# double100.net
KiCad netlist of a schematic drawn in EAGLE
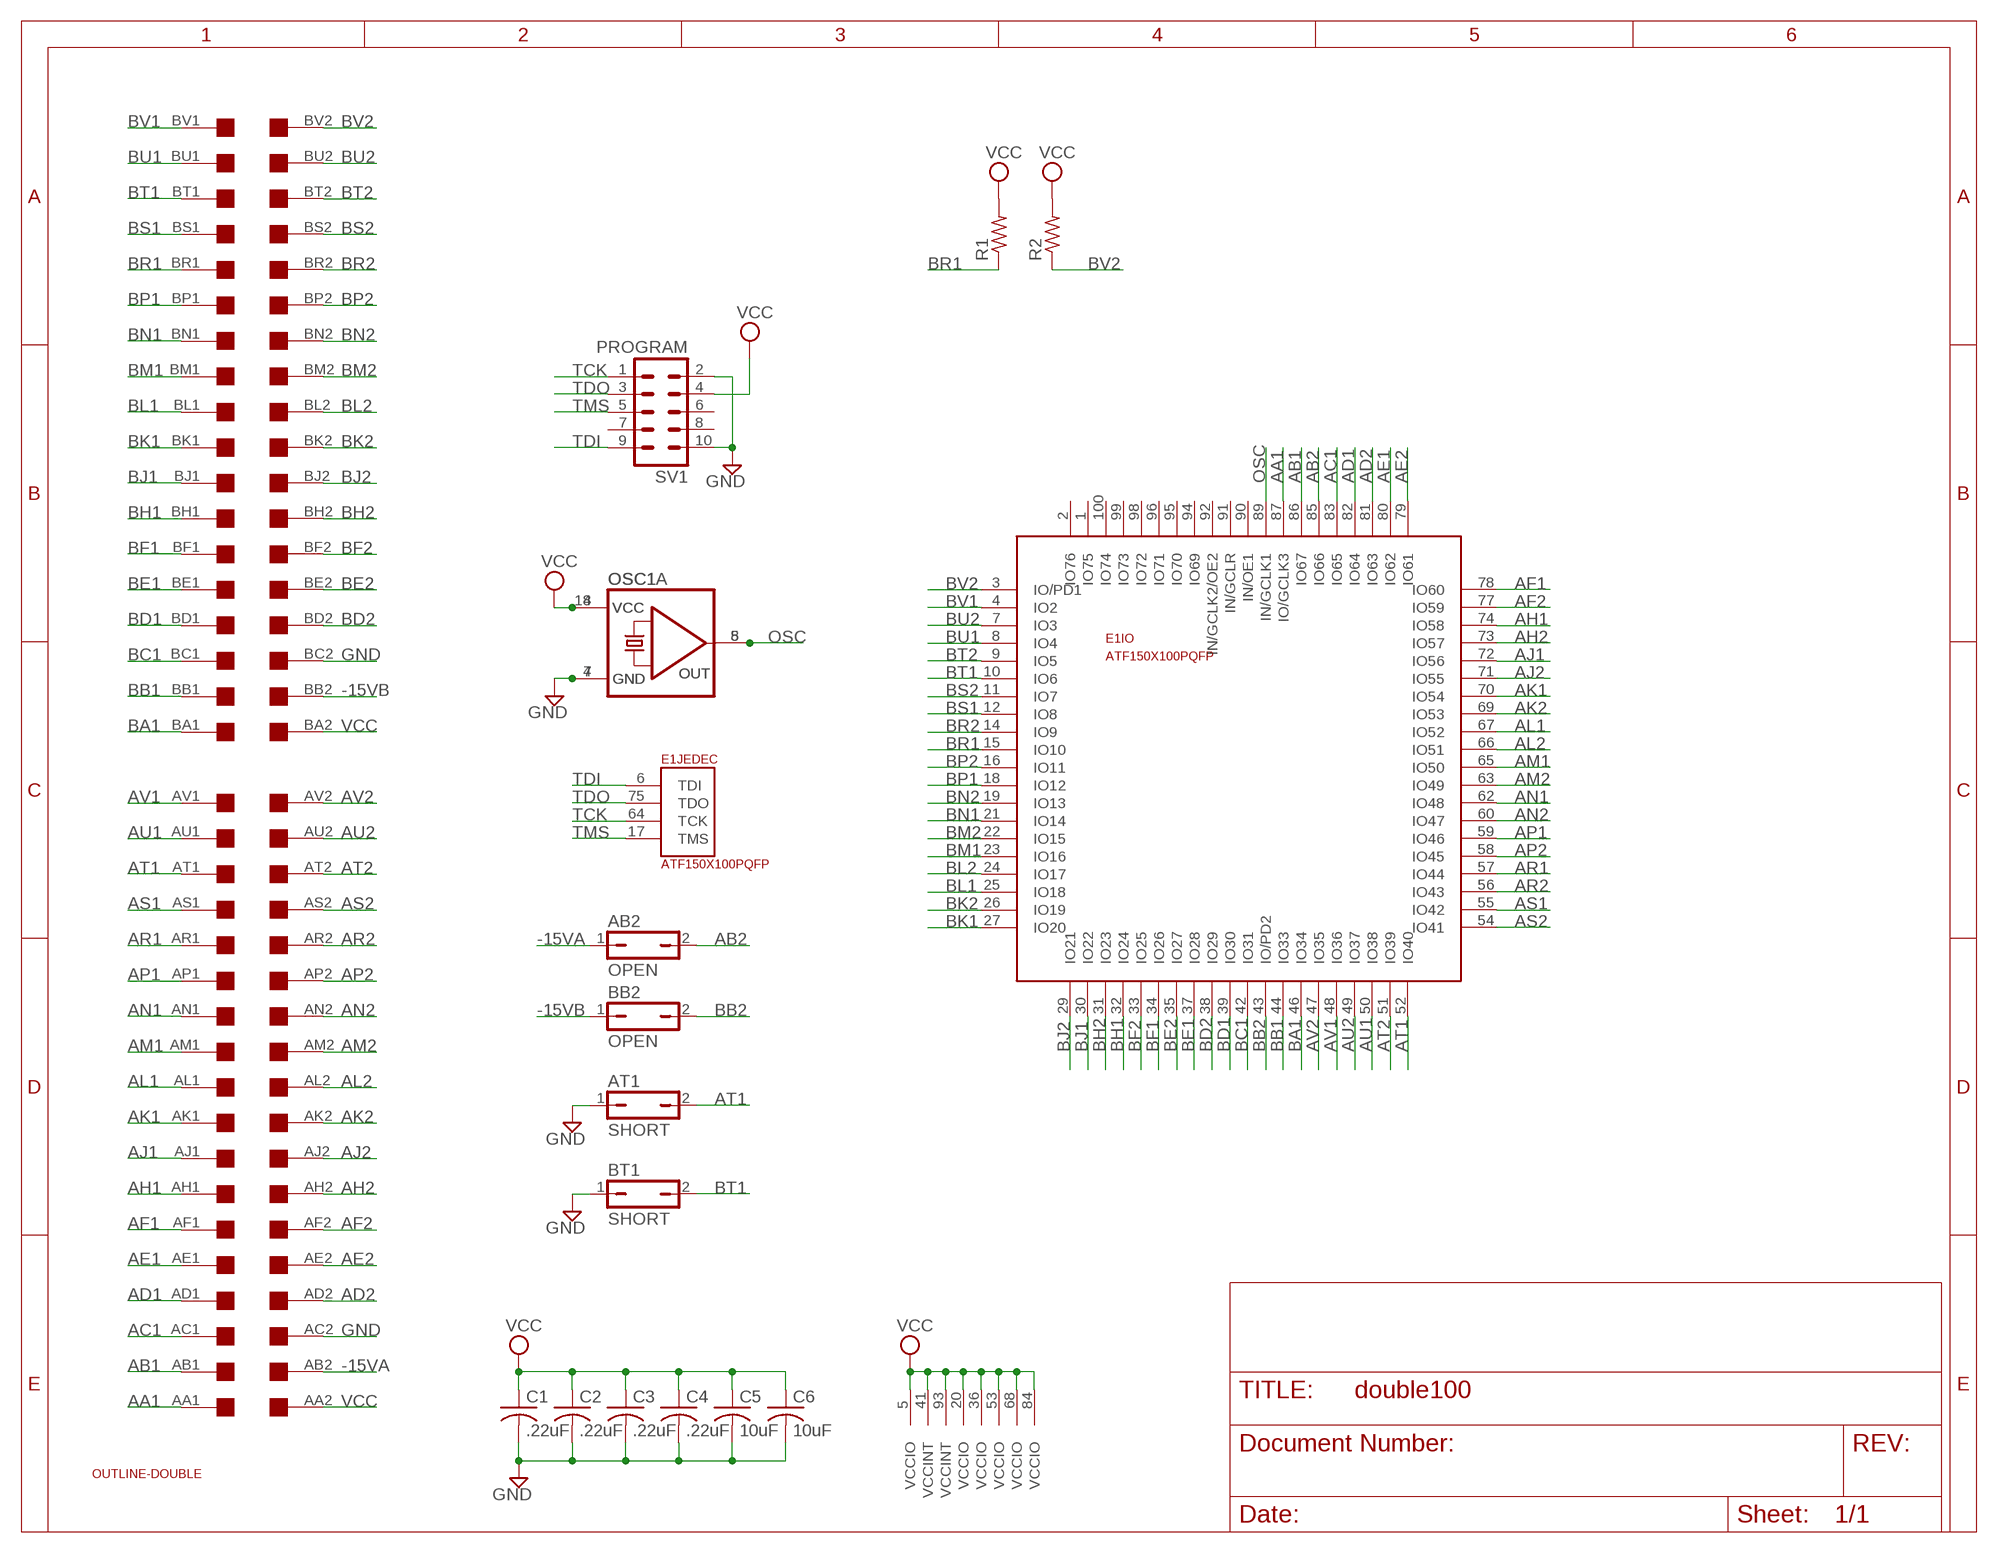
[diagram p0: schematic, sheet 1]

(export (version "E")
  (design (tool "Eeschema 10.0.6"))
  (components
    (comp (ref "AB2")
      (value "OPEN")
      (footprint "eagle-import:JP1")
      (libsource (lib "eagle-import") (part "JP1Q"))
    )
    (comp (ref "AT1")
      (value "SHORT")
      (footprint "eagle-import:JP1")
      (libsource (lib "eagle-import") (part "JP1Q"))
    )
    (comp (ref "BB2")
      (value "OPEN")
      (footprint "eagle-import:JP1")
      (libsource (lib "eagle-import") (part "JP1Q"))
    )
    (comp (ref "BT1")
      (value "SHORT")
      (footprint "eagle-import:JP1")
      (libsource (lib "eagle-import") (part "JP1Q"))
    )
    (comp (ref "C1")
      (value ".22uF")
      (footprint "eagle-import:C0805")
      (libsource (lib "eagle-import") (part "C-USC0805"))
    )
    (comp (ref "C2")
      (value ".22uF")
      (footprint "eagle-import:C0805")
      (libsource (lib "eagle-import") (part "C-USC0805"))
    )
    (comp (ref "C3")
      (value ".22uF")
      (footprint "eagle-import:C0805")
      (libsource (lib "eagle-import") (part "C-USC0805"))
    )
    (comp (ref "C4")
      (value ".22uF")
      (footprint "eagle-import:C0805")
      (libsource (lib "eagle-import") (part "C-USC0805"))
    )
    (comp (ref "C5")
      (value "10uF")
      (footprint "eagle-import:C0805")
      (libsource (lib "eagle-import") (part "C-USC0805"))
    )
    (comp (ref "C6")
      (value "10uF")
      (footprint "eagle-import:C0805")
      (libsource (lib "eagle-import") (part "C-USC0805"))
    )
    (comp (ref "E1")
      (value "ATF150X100PQFP")
      (footprint "eagle-import:PQFP-100")
      (libsource (lib "eagle-import") (part "ATF150X100PQFP"))
    )
    (comp (ref "OSC1")
      (value "QG5460")
      (footprint "eagle-import:DIL08S")
      (libsource (lib "eagle-import") (part "QG5460"))
    )
    (comp (ref "OSC1A")
      (value "QG5860")
      (footprint "eagle-import:DIL14S")
      (libsource (lib "eagle-import") (part "QG5860"))
    )
    (comp (ref "R1")
      (value "R-US_0207/10")
      (footprint "eagle-import:0207_10")
      (libsource (lib "eagle-import") (part "R-US_0207/10"))
    )
    (comp (ref "R2")
      (value "R-US_0207/10")
      (footprint "eagle-import:0207_10")
      (libsource (lib "eagle-import") (part "R-US_0207/10"))
    )
    (comp (ref "SV1")
      (value "PROGRAM")
      (footprint "eagle-import:ML10")
      (libsource (lib "eagle-import") (part "ML10"))
    )
    (comp (ref "U$1")
      (value "DOUBLE")
      (footprint "eagle-import:EDGE-CON4")
      (libsource (lib "eagle-import") (part "DOUBLE"))
    )
    (comp (ref "U$3")
      (value "OUTLINE-DOUBLE")
      (footprint "eagle-import:DOUBLE")
      (libsource (lib "eagle-import") (part "OUTLINE-DOUBLE"))
    )
  )
  (nets
    (net (code "1") (name "/-15VA") (class "Default")
      (node (ref "AB2") (pin "1") (pinfunction "1_1") (pintype "passive"))
      (node (ref "U$1") (pin "AB2") (pinfunction "1_AB2") (pintype "bidirectional"))
    )
    (net (code "2") (name "/-15VB") (class "Default")
      (node (ref "BB2") (pin "1") (pinfunction "1_1") (pintype "passive"))
      (node (ref "U$1") (pin "BB2") (pinfunction "1_BB2") (pintype "bidirectional"))
    )
    (net (code "3") (name "/AA1") (class "Default")
      (node (ref "E1") (pin "87") (pinfunction "IO/GCLK3_87") (pintype "bidirectional"))
      (node (ref "U$1") (pin "AA1") (pinfunction "1_AA1") (pintype "bidirectional"))
    )
    (net (code "4") (name "/AB1") (class "Default")
      (node (ref "E1") (pin "86") (pinfunction "IO67_86") (pintype "bidirectional"))
      (node (ref "U$1") (pin "AB1") (pinfunction "1_AB1") (pintype "bidirectional"))
    )
    (net (code "5") (name "/AB2") (class "Default")
      (node (ref "AB2") (pin "2") (pinfunction "2_2") (pintype "passive"))
      (node (ref "E1") (pin "85") (pinfunction "IO66_85") (pintype "bidirectional"))
    )
    (net (code "6") (name "/AC1") (class "Default")
      (node (ref "E1") (pin "83") (pinfunction "IO65_83") (pintype "bidirectional"))
      (node (ref "U$1") (pin "AC1") (pinfunction "1_AC1") (pintype "bidirectional"))
    )
    (net (code "7") (name "/AD1") (class "Default")
      (node (ref "E1") (pin "82") (pinfunction "IO64_82") (pintype "bidirectional"))
      (node (ref "U$1") (pin "AD1") (pinfunction "1_AD1") (pintype "bidirectional"))
    )
    (net (code "8") (name "/AD2") (class "Default")
      (node (ref "E1") (pin "81") (pinfunction "IO63_81") (pintype "bidirectional"))
      (node (ref "U$1") (pin "AD2") (pinfunction "1_AD2") (pintype "bidirectional"))
    )
    (net (code "9") (name "/AE1") (class "Default")
      (node (ref "E1") (pin "80") (pinfunction "IO62_80") (pintype "bidirectional"))
      (node (ref "U$1") (pin "AE1") (pinfunction "1_AE1") (pintype "bidirectional"))
    )
    (net (code "10") (name "/AE2") (class "Default")
      (node (ref "E1") (pin "79") (pinfunction "IO61_79") (pintype "bidirectional"))
      (node (ref "U$1") (pin "AE2") (pinfunction "1_AE2") (pintype "bidirectional"))
    )
    (net (code "11") (name "/AF1") (class "Default")
      (node (ref "E1") (pin "78") (pinfunction "IO60_78") (pintype "bidirectional"))
      (node (ref "U$1") (pin "AF1") (pinfunction "1_AF1") (pintype "bidirectional"))
    )
    (net (code "12") (name "/AF2") (class "Default")
      (node (ref "E1") (pin "77") (pinfunction "IO59_77") (pintype "bidirectional"))
      (node (ref "U$1") (pin "AF2") (pinfunction "1_AF2") (pintype "bidirectional"))
    )
    (net (code "13") (name "/AH1") (class "Default")
      (node (ref "E1") (pin "74") (pinfunction "IO58_74") (pintype "bidirectional"))
      (node (ref "U$1") (pin "AH1") (pinfunction "1_AH1") (pintype "bidirectional"))
    )
    (net (code "14") (name "/AH2") (class "Default")
      (node (ref "E1") (pin "73") (pinfunction "IO57_73") (pintype "bidirectional"))
      (node (ref "U$1") (pin "AH2") (pinfunction "1_AH2") (pintype "bidirectional"))
    )
    (net (code "15") (name "/AJ1") (class "Default")
      (node (ref "E1") (pin "72") (pinfunction "IO56_72") (pintype "bidirectional"))
      (node (ref "U$1") (pin "AJ1") (pinfunction "1_AJ1") (pintype "bidirectional"))
    )
    (net (code "16") (name "/AJ2") (class "Default")
      (node (ref "E1") (pin "71") (pinfunction "IO55_71") (pintype "bidirectional"))
      (node (ref "U$1") (pin "AJ2") (pinfunction "1_AJ2") (pintype "bidirectional"))
    )
    (net (code "17") (name "/AK1") (class "Default")
      (node (ref "E1") (pin "70") (pinfunction "IO54_70") (pintype "bidirectional"))
      (node (ref "U$1") (pin "AK1") (pinfunction "1_AK1") (pintype "bidirectional"))
    )
    (net (code "18") (name "/AK2") (class "Default")
      (node (ref "E1") (pin "69") (pinfunction "IO53_69") (pintype "bidirectional"))
      (node (ref "U$1") (pin "AK2") (pinfunction "1_AK2") (pintype "bidirectional"))
    )
    (net (code "19") (name "/AL1") (class "Default")
      (node (ref "E1") (pin "67") (pinfunction "IO52_67") (pintype "bidirectional"))
      (node (ref "U$1") (pin "AL1") (pinfunction "1_AL1") (pintype "bidirectional"))
    )
    (net (code "20") (name "/AL2") (class "Default")
      (node (ref "E1") (pin "66") (pinfunction "IO51_66") (pintype "bidirectional"))
      (node (ref "U$1") (pin "AL2") (pinfunction "1_AL2") (pintype "bidirectional"))
    )
    (net (code "21") (name "/AM1") (class "Default")
      (node (ref "E1") (pin "65") (pinfunction "IO50_65") (pintype "bidirectional"))
      (node (ref "U$1") (pin "AM1") (pinfunction "1_AM1") (pintype "bidirectional"))
    )
    (net (code "22") (name "/AM2") (class "Default")
      (node (ref "E1") (pin "63") (pinfunction "IO49_63") (pintype "bidirectional"))
      (node (ref "U$1") (pin "AM2") (pinfunction "1_AM2") (pintype "bidirectional"))
    )
    (net (code "23") (name "/AN1") (class "Default")
      (node (ref "E1") (pin "62") (pinfunction "IO48_62") (pintype "bidirectional"))
      (node (ref "U$1") (pin "AN1") (pinfunction "1_AN1") (pintype "bidirectional"))
    )
    (net (code "24") (name "/AN2") (class "Default")
      (node (ref "E1") (pin "60") (pinfunction "IO47_60") (pintype "bidirectional"))
      (node (ref "U$1") (pin "AN2") (pinfunction "1_AN2") (pintype "bidirectional"))
    )
    (net (code "25") (name "/AP1") (class "Default")
      (node (ref "E1") (pin "59") (pinfunction "IO46_59") (pintype "bidirectional"))
      (node (ref "U$1") (pin "AP1") (pinfunction "1_AP1") (pintype "bidirectional"))
    )
    (net (code "26") (name "/AP2") (class "Default")
      (node (ref "E1") (pin "58") (pinfunction "IO45_58") (pintype "bidirectional"))
      (node (ref "U$1") (pin "AP2") (pinfunction "1_AP2") (pintype "bidirectional"))
    )
    (net (code "27") (name "/AR1") (class "Default")
      (node (ref "E1") (pin "57") (pinfunction "IO44_57") (pintype "bidirectional"))
      (node (ref "U$1") (pin "AR1") (pinfunction "1_AR1") (pintype "bidirectional"))
    )
    (net (code "28") (name "/AR2") (class "Default")
      (node (ref "E1") (pin "56") (pinfunction "IO43_56") (pintype "bidirectional"))
      (node (ref "U$1") (pin "AR2") (pinfunction "1_AR2") (pintype "bidirectional"))
    )
    (net (code "29") (name "/AS1") (class "Default")
      (node (ref "E1") (pin "55") (pinfunction "IO42_55") (pintype "bidirectional"))
      (node (ref "U$1") (pin "AS1") (pinfunction "1_AS1") (pintype "bidirectional"))
    )
    (net (code "30") (name "/AS2") (class "Default")
      (node (ref "E1") (pin "54") (pinfunction "IO41_54") (pintype "bidirectional"))
      (node (ref "U$1") (pin "AS2") (pinfunction "1_AS2") (pintype "bidirectional"))
    )
    (net (code "31") (name "/AT1") (class "Default")
      (node (ref "AT1") (pin "2") (pinfunction "2_2") (pintype "passive"))
      (node (ref "E1") (pin "52") (pinfunction "IO40_52") (pintype "bidirectional"))
      (node (ref "U$1") (pin "AT1") (pinfunction "1_AT1") (pintype "bidirectional"))
    )
    (net (code "32") (name "/AT2") (class "Default")
      (node (ref "E1") (pin "51") (pinfunction "IO39_51") (pintype "bidirectional"))
      (node (ref "U$1") (pin "AT2") (pinfunction "1_AT2") (pintype "bidirectional"))
    )
    (net (code "33") (name "/AU1") (class "Default")
      (node (ref "E1") (pin "50") (pinfunction "IO38_50") (pintype "bidirectional"))
      (node (ref "U$1") (pin "AU1") (pinfunction "1_AU1") (pintype "bidirectional"))
    )
    (net (code "34") (name "/AU2") (class "Default")
      (node (ref "E1") (pin "49") (pinfunction "IO37_49") (pintype "bidirectional"))
      (node (ref "U$1") (pin "AU2") (pinfunction "1_AU2") (pintype "bidirectional"))
    )
    (net (code "35") (name "/AV1") (class "Default")
      (node (ref "E1") (pin "48") (pinfunction "IO36_48") (pintype "bidirectional"))
      (node (ref "U$1") (pin "AV1") (pinfunction "1_AV1") (pintype "bidirectional"))
    )
    (net (code "36") (name "/AV2") (class "Default")
      (node (ref "E1") (pin "47") (pinfunction "IO35_47") (pintype "bidirectional"))
      (node (ref "U$1") (pin "AV2") (pinfunction "1_AV2") (pintype "bidirectional"))
    )
    (net (code "37") (name "/BA1") (class "Default")
      (node (ref "E1") (pin "46") (pinfunction "IO34_46") (pintype "bidirectional"))
      (node (ref "U$1") (pin "BA1") (pinfunction "1_BA1") (pintype "bidirectional"))
    )
    (net (code "38") (name "/BB1") (class "Default")
      (node (ref "E1") (pin "44") (pinfunction "IO33_44") (pintype "bidirectional"))
      (node (ref "U$1") (pin "BB1") (pinfunction "1_BB1") (pintype "bidirectional"))
    )
    (net (code "39") (name "/BB2") (class "Default")
      (node (ref "BB2") (pin "2") (pinfunction "2_2") (pintype "passive"))
      (node (ref "E1") (pin "43") (pinfunction "IO/PD2_43") (pintype "bidirectional"))
    )
    (net (code "40") (name "/BC1") (class "Default")
      (node (ref "E1") (pin "42") (pinfunction "IO31_42") (pintype "bidirectional"))
      (node (ref "U$1") (pin "BC1") (pinfunction "1_BC1") (pintype "bidirectional"))
    )
    (net (code "41") (name "/BD1") (class "Default")
      (node (ref "E1") (pin "39") (pinfunction "IO30_39") (pintype "bidirectional"))
      (node (ref "U$1") (pin "BD1") (pinfunction "1_BD1") (pintype "bidirectional"))
    )
    (net (code "42") (name "/BD2") (class "Default")
      (node (ref "E1") (pin "38") (pinfunction "IO29_38") (pintype "bidirectional"))
      (node (ref "U$1") (pin "BD2") (pinfunction "1_BD2") (pintype "bidirectional"))
    )
    (net (code "43") (name "/BE1") (class "Default")
      (node (ref "E1") (pin "37") (pinfunction "IO28_37") (pintype "bidirectional"))
      (node (ref "U$1") (pin "BE1") (pinfunction "1_BE1") (pintype "bidirectional"))
    )
    (net (code "44") (name "/BE2") (class "Default")
      (node (ref "E1") (pin "35") (pinfunction "IO27_35") (pintype "bidirectional"))
      (node (ref "U$1") (pin "BE2") (pinfunction "1_BE2") (pintype "bidirectional"))
    )
    (net (code "45") (name "/BF1") (class "Default")
      (node (ref "E1") (pin "34") (pinfunction "IO26_34") (pintype "bidirectional"))
      (node (ref "U$1") (pin "BF1") (pinfunction "1_BF1") (pintype "bidirectional"))
    )
    (net (code "46") (name "/BF2") (class "Default")
      (node (ref "E1") (pin "33") (pinfunction "IO25_33") (pintype "bidirectional"))
      (node (ref "U$1") (pin "BF2") (pinfunction "1_BF2") (pintype "bidirectional"))
    )
    (net (code "47") (name "/BH1") (class "Default")
      (node (ref "E1") (pin "32") (pinfunction "IO24_32") (pintype "bidirectional"))
      (node (ref "U$1") (pin "BH1") (pinfunction "1_BH1") (pintype "bidirectional"))
    )
    (net (code "48") (name "/BH2") (class "Default")
      (node (ref "E1") (pin "31") (pinfunction "IO23_31") (pintype "bidirectional"))
      (node (ref "U$1") (pin "BH2") (pinfunction "1_BH2") (pintype "bidirectional"))
    )
    (net (code "49") (name "/BJ1") (class "Default")
      (node (ref "E1") (pin "30") (pinfunction "IO22_30") (pintype "bidirectional"))
      (node (ref "U$1") (pin "BJ1") (pinfunction "1_BJ1") (pintype "bidirectional"))
    )
    (net (code "50") (name "/BJ2") (class "Default")
      (node (ref "E1") (pin "29") (pinfunction "IO21_29") (pintype "bidirectional"))
      (node (ref "U$1") (pin "BJ2") (pinfunction "1_BJ2") (pintype "bidirectional"))
    )
    (net (code "51") (name "/BK1") (class "Default")
      (node (ref "E1") (pin "27") (pinfunction "IO20_27") (pintype "bidirectional"))
      (node (ref "U$1") (pin "BK1") (pinfunction "1_BK1") (pintype "bidirectional"))
    )
    (net (code "52") (name "/BK2") (class "Default")
      (node (ref "E1") (pin "26") (pinfunction "IO19_26") (pintype "bidirectional"))
      (node (ref "U$1") (pin "BK2") (pinfunction "1_BK2") (pintype "bidirectional"))
    )
    (net (code "53") (name "/BL1") (class "Default")
      (node (ref "E1") (pin "25") (pinfunction "IO18_25") (pintype "bidirectional"))
      (node (ref "U$1") (pin "BL1") (pinfunction "1_BL1") (pintype "bidirectional"))
    )
    (net (code "54") (name "/BL2") (class "Default")
      (node (ref "E1") (pin "24") (pinfunction "IO17_24") (pintype "bidirectional"))
      (node (ref "U$1") (pin "BL2") (pinfunction "1_BL2") (pintype "bidirectional"))
    )
    (net (code "55") (name "/BM1") (class "Default")
      (node (ref "E1") (pin "23") (pinfunction "IO16_23") (pintype "bidirectional"))
      (node (ref "U$1") (pin "BM1") (pinfunction "1_BM1") (pintype "bidirectional"))
    )
    (net (code "56") (name "/BM2") (class "Default")
      (node (ref "E1") (pin "22") (pinfunction "IO15_22") (pintype "bidirectional"))
      (node (ref "U$1") (pin "BM2") (pinfunction "1_BM2") (pintype "bidirectional"))
    )
    (net (code "57") (name "/BN1") (class "Default")
      (node (ref "E1") (pin "21") (pinfunction "IO14_21") (pintype "bidirectional"))
      (node (ref "U$1") (pin "BN1") (pinfunction "1_BN1") (pintype "bidirectional"))
    )
    (net (code "58") (name "/BN2") (class "Default")
      (node (ref "E1") (pin "19") (pinfunction "IO13_19") (pintype "bidirectional"))
      (node (ref "U$1") (pin "BN2") (pinfunction "1_BN2") (pintype "bidirectional"))
    )
    (net (code "59") (name "/BP1") (class "Default")
      (node (ref "E1") (pin "18") (pinfunction "IO12_18") (pintype "bidirectional"))
      (node (ref "U$1") (pin "BP1") (pinfunction "1_BP1") (pintype "bidirectional"))
    )
    (net (code "60") (name "/BP2") (class "Default")
      (node (ref "E1") (pin "16") (pinfunction "IO11_16") (pintype "bidirectional"))
      (node (ref "U$1") (pin "BP2") (pinfunction "1_BP2") (pintype "bidirectional"))
    )
    (net (code "61") (name "/BR1") (class "Default")
      (node (ref "E1") (pin "15") (pinfunction "IO10_15") (pintype "bidirectional"))
      (node (ref "R1") (pin "1") (pinfunction "1_1") (pintype "passive"))
      (node (ref "U$1") (pin "BR1") (pinfunction "1_BR1") (pintype "bidirectional"))
    )
    (net (code "62") (name "/BR2") (class "Default")
      (node (ref "E1") (pin "14") (pinfunction "IO9_14") (pintype "bidirectional"))
      (node (ref "U$1") (pin "BR2") (pinfunction "1_BR2") (pintype "bidirectional"))
    )
    (net (code "63") (name "/BS1") (class "Default")
      (node (ref "E1") (pin "12") (pinfunction "IO8_12") (pintype "bidirectional"))
      (node (ref "U$1") (pin "BS1") (pinfunction "1_BS1") (pintype "bidirectional"))
    )
    (net (code "64") (name "/BS2") (class "Default")
      (node (ref "E1") (pin "11") (pinfunction "IO7_11") (pintype "bidirectional"))
      (node (ref "U$1") (pin "BS2") (pinfunction "1_BS2") (pintype "bidirectional"))
    )
    (net (code "65") (name "/BT1") (class "Default")
      (node (ref "BT1") (pin "2") (pinfunction "2_2") (pintype "passive"))
      (node (ref "E1") (pin "10") (pinfunction "IO6_10") (pintype "bidirectional"))
      (node (ref "U$1") (pin "BT1") (pinfunction "1_BT1") (pintype "bidirectional"))
    )
    (net (code "66") (name "/BT2") (class "Default")
      (node (ref "E1") (pin "9") (pinfunction "IO5_9") (pintype "bidirectional"))
      (node (ref "U$1") (pin "BT2") (pinfunction "1_BT2") (pintype "bidirectional"))
    )
    (net (code "67") (name "/BU1") (class "Default")
      (node (ref "E1") (pin "8") (pinfunction "IO4_8") (pintype "bidirectional"))
      (node (ref "U$1") (pin "BU1") (pinfunction "1_BU1") (pintype "bidirectional"))
    )
    (net (code "68") (name "/BU2") (class "Default")
      (node (ref "E1") (pin "7") (pinfunction "IO3_7") (pintype "bidirectional"))
      (node (ref "U$1") (pin "BU2") (pinfunction "1_BU2") (pintype "bidirectional"))
    )
    (net (code "69") (name "/BV1") (class "Default")
      (node (ref "E1") (pin "4") (pinfunction "IO2_4") (pintype "bidirectional"))
      (node (ref "U$1") (pin "BV1") (pinfunction "1_BV1") (pintype "bidirectional"))
    )
    (net (code "70") (name "/BV2") (class "Default")
      (node (ref "E1") (pin "3") (pinfunction "IO/PD1_3") (pintype "bidirectional"))
      (node (ref "R2") (pin "1") (pinfunction "1_1") (pintype "passive"))
      (node (ref "U$1") (pin "BV2") (pinfunction "1_BV2") (pintype "bidirectional"))
    )
    (net (code "71") (name "/OSC") (class "Default")
      (node (ref "E1") (pin "89") (pinfunction "IN/GCLK1_89") (pintype "input"))
      (node (ref "OSC1") (pin "5") (pinfunction "OUT_5") (pintype "output"))
      (node (ref "OSC1A") (pin "8") (pinfunction "OUT_8") (pintype "output"))
    )
    (net (code "72") (name "/TCK") (class "Default")
      (node (ref "E1") (pin "64") (pinfunction "TCK_64") (pintype "bidirectional"))
      (node (ref "SV1") (pin "1") (pinfunction "1_1") (pintype "passive"))
    )
    (net (code "73") (name "/TDI") (class "Default")
      (node (ref "E1") (pin "6") (pinfunction "TDI_6") (pintype "bidirectional"))
      (node (ref "SV1") (pin "9") (pinfunction "9_9") (pintype "passive"))
    )
    (net (code "74") (name "/TDO") (class "Default")
      (node (ref "E1") (pin "75") (pinfunction "TDO_75") (pintype "bidirectional"))
      (node (ref "SV1") (pin "3") (pinfunction "3_3") (pintype "passive"))
    )
    (net (code "75") (name "/TMS") (class "Default")
      (node (ref "E1") (pin "17") (pinfunction "TMS_17") (pintype "bidirectional"))
      (node (ref "SV1") (pin "5") (pinfunction "5_5") (pintype "passive"))
    )
    (net (code "76") (name "GND") (class "Default")
      (node (ref "AT1") (pin "1") (pinfunction "1_1") (pintype "passive"))
      (node (ref "BT1") (pin "1") (pinfunction "1_1") (pintype "passive"))
      (node (ref "C1") (pin "2") (pinfunction "2_2") (pintype "passive"))
      (node (ref "C2") (pin "2") (pinfunction "2_2") (pintype "passive"))
      (node (ref "C3") (pin "2") (pinfunction "2_2") (pintype "passive"))
      (node (ref "C4") (pin "2") (pinfunction "2_2") (pintype "passive"))
      (node (ref "C5") (pin "2") (pinfunction "2_2") (pintype "passive"))
      (node (ref "C6") (pin "2") (pinfunction "2_2") (pintype "passive"))
      (node (ref "OSC1") (pin "4") (pinfunction "GND_4") (pintype "power_in"))
      (node (ref "OSC1A") (pin "7") (pinfunction "GND_7") (pintype "power_in"))
      (node (ref "SV1") (pin "10") (pinfunction "10_10") (pintype "passive"))
      (node (ref "SV1") (pin "2") (pinfunction "2_2") (pintype "passive"))
      (node (ref "U$1") (pin "AC2") (pinfunction "1_AC2") (pintype "bidirectional"))
      (node (ref "U$1") (pin "BC2") (pinfunction "1_BC2") (pintype "bidirectional"))
    )
    (net (code "77") (name "VCC") (class "Default")
      (node (ref "C1") (pin "1") (pinfunction "1_1") (pintype "passive"))
      (node (ref "C2") (pin "1") (pinfunction "1_1") (pintype "passive"))
      (node (ref "C3") (pin "1") (pinfunction "1_1") (pintype "passive"))
      (node (ref "C4") (pin "1") (pinfunction "1_1") (pintype "passive"))
      (node (ref "C5") (pin "1") (pinfunction "1_1") (pintype "passive"))
      (node (ref "C6") (pin "1") (pinfunction "1_1") (pintype "passive"))
      (node (ref "E1") (pin "20") (pinfunction "VCCIO_20") (pintype "power_in"))
      (node (ref "E1") (pin "36") (pinfunction "VCCIO_36") (pintype "power_in"))
      (node (ref "E1") (pin "41") (pinfunction "VCCINT_41") (pintype "power_in"))
      (node (ref "E1") (pin "5") (pinfunction "VCCIO_5") (pintype "power_in"))
      (node (ref "E1") (pin "53") (pinfunction "VCCIO_53") (pintype "power_in"))
      (node (ref "E1") (pin "68") (pinfunction "VCCIO_68") (pintype "power_in"))
      (node (ref "E1") (pin "84") (pinfunction "VCCIO_84") (pintype "power_in"))
      (node (ref "E1") (pin "93") (pinfunction "VCCINT_93") (pintype "power_in"))
      (node (ref "OSC1") (pin "8") (pinfunction "VCC_8") (pintype "power_in"))
      (node (ref "OSC1A") (pin "14") (pinfunction "VCC_14") (pintype "power_in"))
      (node (ref "R1") (pin "2") (pinfunction "2_2") (pintype "passive"))
      (node (ref "R2") (pin "2") (pinfunction "2_2") (pintype "passive"))
      (node (ref "SV1") (pin "4") (pinfunction "4_4") (pintype "passive"))
      (node (ref "U$1") (pin "AA2") (pinfunction "1_AA2") (pintype "bidirectional"))
      (node (ref "U$1") (pin "BA2") (pinfunction "1_BA2") (pintype "bidirectional"))
    )
    (net (code "78") (name "unconnected-(E1Q-IN{slash}GCLK2{slash}OE2-Pad92)") (class "Default")
      (node (ref "E1") (pin "92") (pinfunction "IN/GCLK2/OE2_92") (pintype "input"))
    )
    (net (code "79") (name "unconnected-(E1Q-IN{slash}GCLR-Pad91)") (class "Default")
      (node (ref "E1") (pin "91") (pinfunction "IN/GCLR_91") (pintype "input"))
    )
    (net (code "80") (name "unconnected-(E1Q-IN{slash}OE1-Pad90)") (class "Default")
      (node (ref "E1") (pin "90") (pinfunction "IN/OE1_90") (pintype "input"))
    )
    (net (code "81") (name "unconnected-(E1Q-IO69-Pad94)") (class "Default")
      (node (ref "E1") (pin "94") (pinfunction "IO69_94") (pintype "bidirectional"))
    )
    (net (code "82") (name "unconnected-(E1Q-IO70-Pad95)") (class "Default")
      (node (ref "E1") (pin "95") (pinfunction "IO70_95") (pintype "bidirectional"))
    )
    (net (code "83") (name "unconnected-(E1Q-IO71-Pad96)") (class "Default")
      (node (ref "E1") (pin "96") (pinfunction "IO71_96") (pintype "bidirectional"))
    )
    (net (code "84") (name "unconnected-(E1Q-IO72-Pad98)") (class "Default")
      (node (ref "E1") (pin "98") (pinfunction "IO72_98") (pintype "bidirectional"))
    )
    (net (code "85") (name "unconnected-(E1Q-IO73-Pad99)") (class "Default")
      (node (ref "E1") (pin "99") (pinfunction "IO73_99") (pintype "bidirectional"))
    )
    (net (code "86") (name "unconnected-(E1Q-IO74-Pad100)") (class "Default")
      (node (ref "E1") (pin "100") (pinfunction "IO74_100") (pintype "bidirectional"))
    )
    (net (code "87") (name "unconnected-(E1Q-IO75-Pad1)") (class "Default")
      (node (ref "E1") (pin "1") (pinfunction "IO75_1") (pintype "bidirectional"))
    )
    (net (code "88") (name "unconnected-(E1Q-IO76-Pad2)") (class "Default")
      (node (ref "E1") (pin "2") (pinfunction "IO76_2") (pintype "bidirectional"))
    )
    (net (code "89") (name "unconnected-(SV1-Pad6)") (class "Default")
      (node (ref "SV1") (pin "6") (pinfunction "6_6") (pintype "passive"))
    )
    (net (code "90") (name "unconnected-(SV1-Pad7)") (class "Default")
      (node (ref "SV1") (pin "7") (pinfunction "7_7") (pintype "passive"))
    )
    (net (code "91") (name "unconnected-(SV1-Pad8)") (class "Default")
      (node (ref "SV1") (pin "8") (pinfunction "8_8") (pintype "passive"))
    )
  )
)
